# SilentStepStick-TMC2208_v13.net
KiCad netlist of a schematic drawn in EAGLE
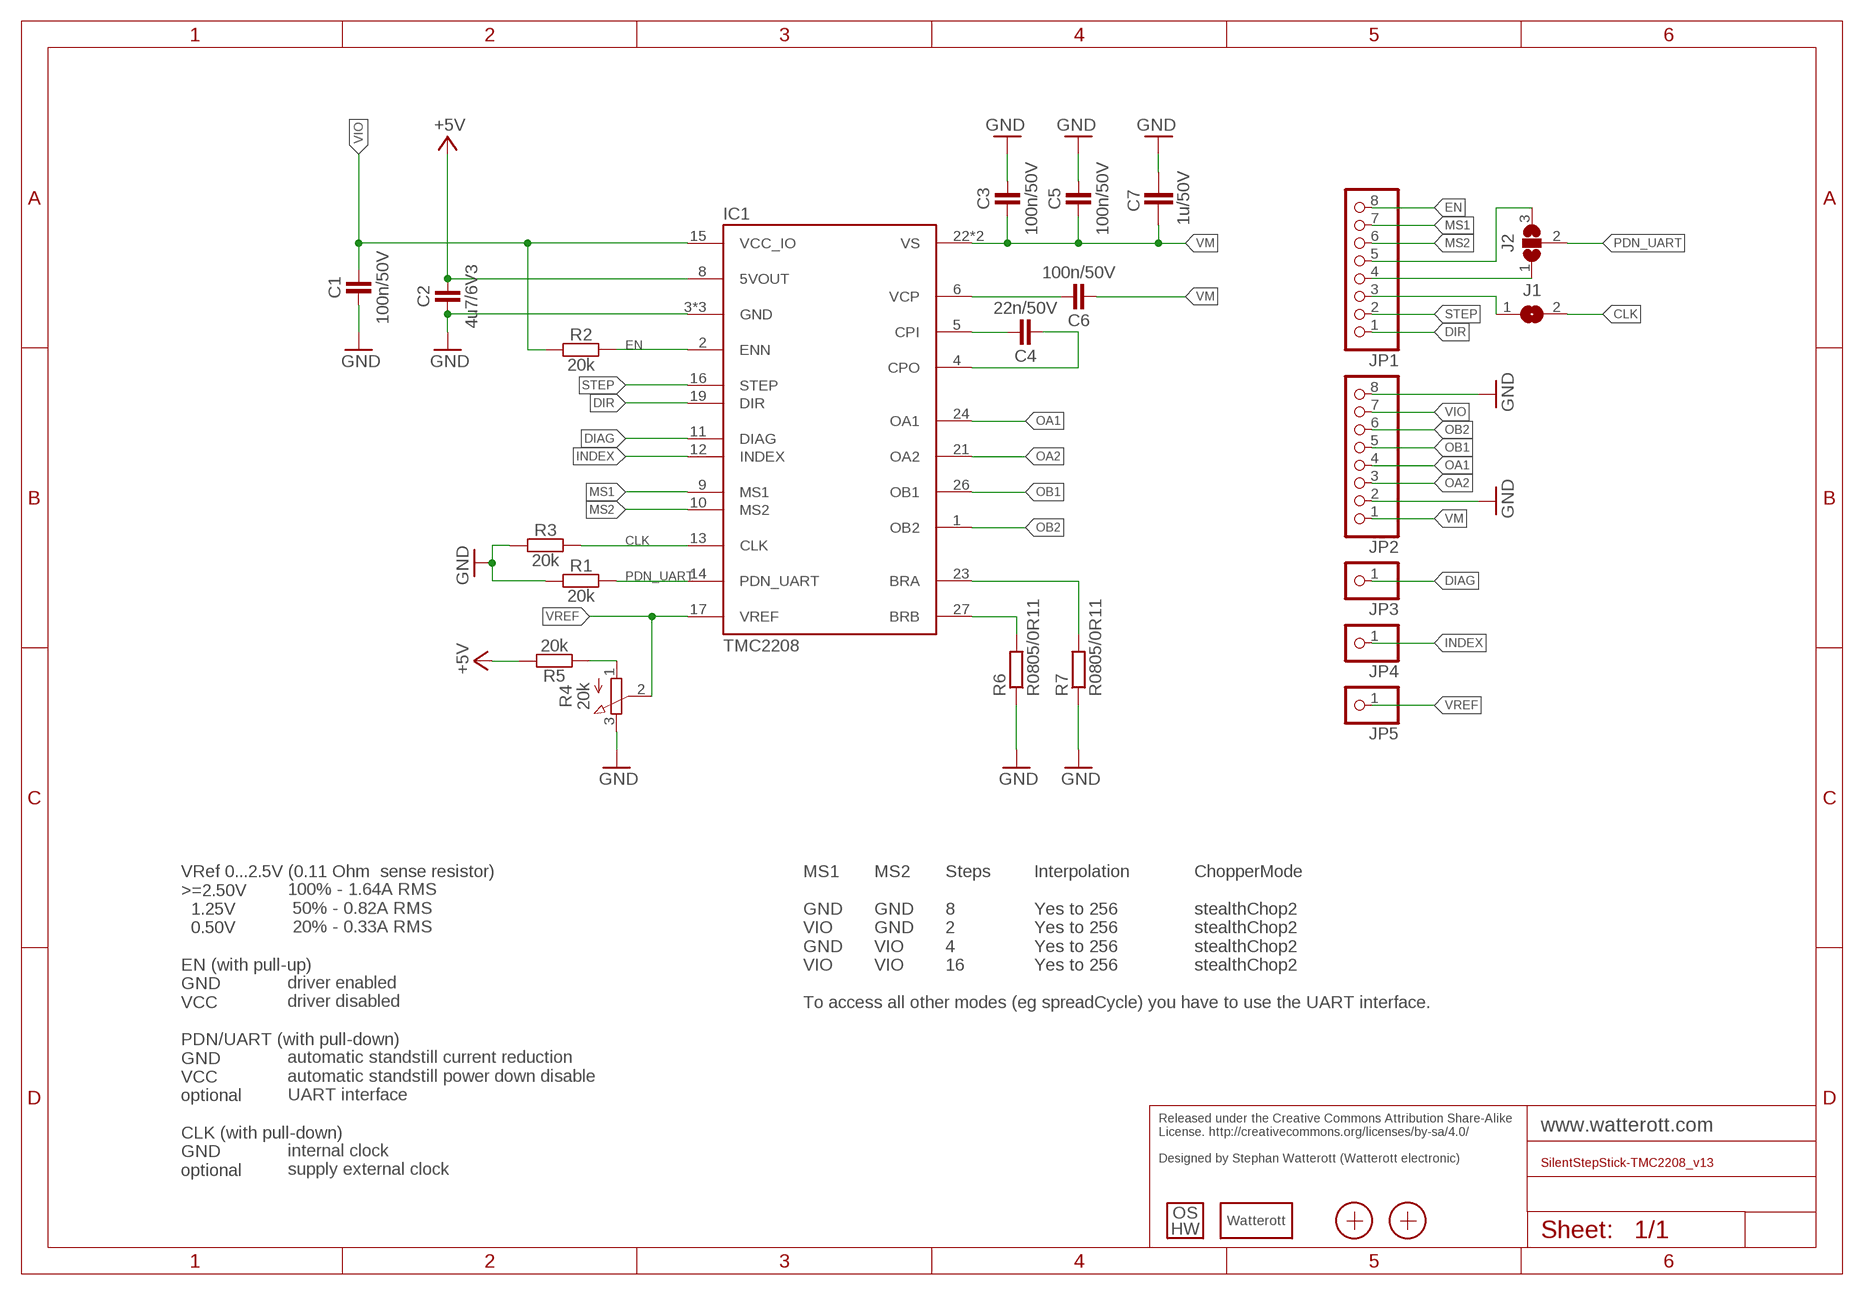
[diagram p0: schematic, sheet 1]

(export (version "E")
  (design (tool "Eeschema 10.0.6"))
  (components
    (comp (ref "C1")
      (value "100n/50V")
      (footprint "eagle-import:C0402")
      (libsource (lib "eagle-import") (part "CAPACITOR-0402"))
    )
    (comp (ref "C2")
      (value "4u7/6V3")
      (footprint "eagle-import:C0402")
      (libsource (lib "eagle-import") (part "CAPACITOR-0402"))
    )
    (comp (ref "C3")
      (value "100n/50V")
      (footprint "eagle-import:C0402")
      (libsource (lib "eagle-import") (part "CAPACITOR-0402"))
    )
    (comp (ref "C4")
      (value "22n/50V")
      (footprint "eagle-import:C0402")
      (libsource (lib "eagle-import") (part "CAPACITOR-0402"))
    )
    (comp (ref "C5")
      (value "100n/50V")
      (footprint "eagle-import:C0402")
      (libsource (lib "eagle-import") (part "CAPACITOR-0402"))
    )
    (comp (ref "C6")
      (value "100n/50V")
      (footprint "eagle-import:C0402")
      (libsource (lib "eagle-import") (part "CAPACITOR-0402"))
    )
    (comp (ref "C7")
      (value "1u/50V")
      (footprint "eagle-import:C0805")
      (libsource (lib "eagle-import") (part "C-EUC0805"))
    )
    (comp (ref "IC1")
      (value "TMC2208")
      (footprint "eagle-import:QFN28-PAD")
      (libsource (lib "eagle-import") (part "TMC2208"))
    )
    (comp (ref "J1")
      (value "JUMPER2-0402")
      (footprint "eagle-import:JUMPER2-0402")
      (libsource (lib "eagle-import") (part "JUMPER2-0402"))
    )
    (comp (ref "J2")
      (value "JUMPER3-0402-NC")
      (footprint "eagle-import:JUMPER3-0402_NC")
      (libsource (lib "eagle-import") (part "JUMPER3-0402-NC"))
    )
    (comp (ref "JP1")
      (value "PINHD-1X08_2.54-S")
      (footprint "eagle-import:1X08-S")
      (libsource (lib "eagle-import") (part "PINHD-1X08_2.54-S"))
    )
    (comp (ref "JP2")
      (value "PINHD-1X08_2.54-S")
      (footprint "eagle-import:1X08-S")
      (libsource (lib "eagle-import") (part "PINHD-1X08_2.54-S"))
    )
    (comp (ref "JP3")
      (value "PINHD-1X1")
      (footprint "eagle-import:1X01")
      (libsource (lib "eagle-import") (part "PINHD-1X1"))
    )
    (comp (ref "JP4")
      (value "PINHD-1X1")
      (footprint "eagle-import:1X01")
      (libsource (lib "eagle-import") (part "PINHD-1X1"))
    )
    (comp (ref "JP5")
      (value "PINHD-1X1")
      (footprint "eagle-import:1X01")
      (libsource (lib "eagle-import") (part "PINHD-1X1"))
    )
    (comp (ref "LOGO3")
      (value "LOGO_SPARK-2")
      (footprint "eagle-import:SPARK_2MM")
      (libsource (lib "eagle-import") (part "LOGO_SPARK-2"))
    )
    (comp (ref "LOGO4")
      (value "LOGO_OSHW-2")
      (footprint "eagle-import:OSHW_2MM")
      (libsource (lib "eagle-import") (part "LOGO_OSHW-2"))
    )
    (comp (ref "R1")
      (value "20k")
      (footprint "eagle-import:C0402")
      (libsource (lib "eagle-import") (part "RESISTOR-0402"))
    )
    (comp (ref "R2")
      (value "20k")
      (footprint "eagle-import:C0402")
      (libsource (lib "eagle-import") (part "RESISTOR-0402"))
    )
    (comp (ref "R3")
      (value "20k")
      (footprint "eagle-import:C0402")
      (libsource (lib "eagle-import") (part "RESISTOR-0402"))
    )
    (comp (ref "R4")
      (value "20k")
      (footprint "eagle-import:POT_EVM3R")
      (libsource (lib "eagle-import") (part "POT-EVM3R"))
    )
    (comp (ref "R5")
      (value "20k")
      (footprint "eagle-import:C0402")
      (libsource (lib "eagle-import") (part "RESISTOR-0402"))
    )
    (comp (ref "R6")
      (value "R0805/0R11")
      (footprint "eagle-import:M0805")
      (libsource (lib "eagle-import") (part "R-EU_M0805"))
    )
    (comp (ref "R7")
      (value "R0805/0R11")
      (footprint "eagle-import:M0805")
      (libsource (lib "eagle-import") (part "R-EU_M0805"))
    )
    (comp (ref "X1")
      (value "PASSER-04")
      (footprint "eagle-import:PASSER_04MM")
      (libsource (lib "eagle-import") (part "PASSER-04"))
    )
    (comp (ref "X2")
      (value "PASSER-04")
      (footprint "eagle-import:PASSER_04MM")
      (libsource (lib "eagle-import") (part "PASSER-04"))
    )
  )
  (nets
    (net (code "1") (name "+5V") (class "Default")
      (node (ref "C2") (pin "2") (pinfunction "2_2") (pintype "passive"))
      (node (ref "IC1") (pin "8") (pinfunction "5VOUT_8") (pintype "power_in"))
      (node (ref "R5") (pin "2") (pinfunction "2_2") (pintype "passive"))
    )
    (net (code "2") (name "CLK") (class "Default")
      (node (ref "IC1") (pin "13") (pinfunction "CLK_13") (pintype "bidirectional"))
      (node (ref "J1") (pin "2") (pinfunction "2_2") (pintype "passive"))
      (node (ref "R3") (pin "2") (pinfunction "2_2") (pintype "passive"))
    )
    (net (code "3") (name "DIAG") (class "Default")
      (node (ref "IC1") (pin "11") (pinfunction "DIAG_11") (pintype "bidirectional"))
      (node (ref "JP3") (pin "1") (pinfunction "1_1") (pintype "passive"))
    )
    (net (code "4") (name "DIR") (class "Default")
      (node (ref "IC1") (pin "19") (pinfunction "DIR_19") (pintype "bidirectional"))
      (node (ref "JP1") (pin "1") (pinfunction "1_1") (pintype "passive"))
    )
    (net (code "5") (name "EN") (class "Default")
      (node (ref "IC1") (pin "2") (pinfunction "ENN_2") (pintype "bidirectional"))
      (node (ref "JP1") (pin "8") (pinfunction "8_8") (pintype "passive"))
      (node (ref "R2") (pin "2") (pinfunction "2_2") (pintype "passive"))
    )
    (net (code "6") (name "GND") (class "Default")
      (node (ref "C1") (pin "1") (pinfunction "1_1") (pintype "passive"))
      (node (ref "C2") (pin "1") (pinfunction "1_1") (pintype "passive"))
      (node (ref "C3") (pin "2") (pinfunction "2_2") (pintype "passive"))
      (node (ref "C5") (pin "2") (pinfunction "2_2") (pintype "passive"))
      (node (ref "C7") (pin "2") (pinfunction "2_2") (pintype "passive"))
      (node (ref "IC1") (pin "18") (pinfunction "GND_18") (pintype "power_in"))
      (node (ref "IC1") (pin "3") (pinfunction "GND_3") (pintype "power_in"))
      (node (ref "IC1") (pin "TP") (pinfunction "GND_TP") (pintype "power_in"))
      (node (ref "JP2") (pin "2") (pinfunction "2_2") (pintype "passive"))
      (node (ref "JP2") (pin "8") (pinfunction "8_8") (pintype "passive"))
      (node (ref "R1") (pin "1") (pinfunction "1_1") (pintype "passive"))
      (node (ref "R3") (pin "1") (pinfunction "1_1") (pintype "passive"))
      (node (ref "R4") (pin "3") (pinfunction "E_3") (pintype "passive"))
      (node (ref "R6") (pin "1") (pinfunction "1_1") (pintype "passive"))
      (node (ref "R7") (pin "1") (pinfunction "1_1") (pintype "passive"))
    )
    (net (code "7") (name "INDEX") (class "Default")
      (node (ref "IC1") (pin "12") (pinfunction "INDEX_12") (pintype "bidirectional"))
      (node (ref "JP4") (pin "1") (pinfunction "1_1") (pintype "passive"))
    )
    (net (code "8") (name "MS1") (class "Default")
      (node (ref "IC1") (pin "9") (pinfunction "MS1_9") (pintype "bidirectional"))
      (node (ref "JP1") (pin "7") (pinfunction "7_7") (pintype "passive"))
    )
    (net (code "9") (name "MS2") (class "Default")
      (node (ref "IC1") (pin "10") (pinfunction "MS2_10") (pintype "bidirectional"))
      (node (ref "JP1") (pin "6") (pinfunction "6_6") (pintype "passive"))
    )
    (net (code "10") (name "Net-(IC1-BRA)") (class "Default")
      (node (ref "IC1") (pin "23") (pinfunction "BRA_23") (pintype "output"))
      (node (ref "R7") (pin "2") (pinfunction "2_2") (pintype "passive"))
    )
    (net (code "11") (name "Net-(IC1-BRB)") (class "Default")
      (node (ref "IC1") (pin "27") (pinfunction "BRB_27") (pintype "output"))
      (node (ref "R6") (pin "2") (pinfunction "2_2") (pintype "passive"))
    )
    (net (code "12") (name "Net-(IC1-CPI)") (class "Default")
      (node (ref "C4") (pin "2") (pinfunction "2_2") (pintype "passive"))
      (node (ref "IC1") (pin "5") (pinfunction "CPI_5") (pintype "passive"))
    )
    (net (code "13") (name "Net-(IC1-CPO)") (class "Default")
      (node (ref "C4") (pin "1") (pinfunction "1_1") (pintype "passive"))
      (node (ref "IC1") (pin "4") (pinfunction "CPO_4") (pintype "passive"))
    )
    (net (code "14") (name "Net-(IC1-VCP)") (class "Default")
      (node (ref "C6") (pin "2") (pinfunction "2_2") (pintype "passive"))
      (node (ref "IC1") (pin "6") (pinfunction "VCP_6") (pintype "passive"))
    )
    (net (code "15") (name "Net-(J1-Pad1)") (class "Default")
      (node (ref "J1") (pin "1") (pinfunction "1_1") (pintype "passive"))
      (node (ref "JP1") (pin "3") (pinfunction "3_3") (pintype "passive"))
    )
    (net (code "16") (name "Net-(J2-Pad1)") (class "Default")
      (node (ref "J2") (pin "1") (pinfunction "1_1") (pintype "passive"))
      (node (ref "JP1") (pin "4") (pinfunction "4_4") (pintype "passive"))
    )
    (net (code "17") (name "Net-(J2-Pad3)") (class "Default")
      (node (ref "J2") (pin "3") (pinfunction "3_3") (pintype "passive"))
      (node (ref "JP1") (pin "5") (pinfunction "5_5") (pintype "passive"))
    )
    (net (code "18") (name "Net-(R4-A)") (class "Default")
      (node (ref "R4") (pin "1") (pinfunction "A_1") (pintype "passive"))
      (node (ref "R5") (pin "1") (pinfunction "1_1") (pintype "passive"))
    )
    (net (code "19") (name "OA1") (class "Default")
      (node (ref "IC1") (pin "24") (pinfunction "OA1_24") (pintype "output"))
      (node (ref "JP2") (pin "4") (pinfunction "4_4") (pintype "passive"))
    )
    (net (code "20") (name "OA2") (class "Default")
      (node (ref "IC1") (pin "21") (pinfunction "OA2_21") (pintype "output"))
      (node (ref "JP2") (pin "3") (pinfunction "3_3") (pintype "passive"))
    )
    (net (code "21") (name "OB1") (class "Default")
      (node (ref "IC1") (pin "26") (pinfunction "OB1_26") (pintype "output"))
      (node (ref "JP2") (pin "5") (pinfunction "5_5") (pintype "passive"))
    )
    (net (code "22") (name "OB2") (class "Default")
      (node (ref "IC1") (pin "1") (pinfunction "OB2_1") (pintype "output"))
      (node (ref "JP2") (pin "6") (pinfunction "6_6") (pintype "passive"))
    )
    (net (code "23") (name "PDN_UART") (class "Default")
      (node (ref "IC1") (pin "14") (pinfunction "PDN_UART_14") (pintype "bidirectional"))
      (node (ref "J2") (pin "2") (pinfunction "2_2") (pintype "passive"))
      (node (ref "R1") (pin "2") (pinfunction "2_2") (pintype "passive"))
    )
    (net (code "24") (name "STEP") (class "Default")
      (node (ref "IC1") (pin "16") (pinfunction "STEP_16") (pintype "bidirectional"))
      (node (ref "JP1") (pin "2") (pinfunction "2_2") (pintype "passive"))
    )
    (net (code "25") (name "VIO") (class "Default")
      (node (ref "C1") (pin "2") (pinfunction "2_2") (pintype "passive"))
      (node (ref "IC1") (pin "15") (pinfunction "VCC_IO_15") (pintype "power_in"))
      (node (ref "JP2") (pin "7") (pinfunction "7_7") (pintype "passive"))
      (node (ref "R2") (pin "1") (pinfunction "1_1") (pintype "passive"))
    )
    (net (code "26") (name "VM") (class "Default")
      (node (ref "C3") (pin "1") (pinfunction "1_1") (pintype "passive"))
      (node (ref "C5") (pin "1") (pinfunction "1_1") (pintype "passive"))
      (node (ref "C6") (pin "1") (pinfunction "1_1") (pintype "passive"))
      (node (ref "C7") (pin "1") (pinfunction "1_1") (pintype "passive"))
      (node (ref "IC1") (pin "22") (pinfunction "VS_22") (pintype "power_in"))
      (node (ref "IC1") (pin "28") (pinfunction "VS_28") (pintype "power_in"))
      (node (ref "JP2") (pin "1") (pinfunction "1_1") (pintype "passive"))
    )
    (net (code "27") (name "VREF") (class "Default")
      (node (ref "IC1") (pin "17") (pinfunction "VREF_17") (pintype "passive"))
      (node (ref "JP5") (pin "1") (pinfunction "1_1") (pintype "passive"))
      (node (ref "R4") (pin "2") (pinfunction "S_2") (pintype "passive"))
    )
  )
)
